# MB_Sheet1.net
KiCad netlist of a schematic drawn in Altium Designer
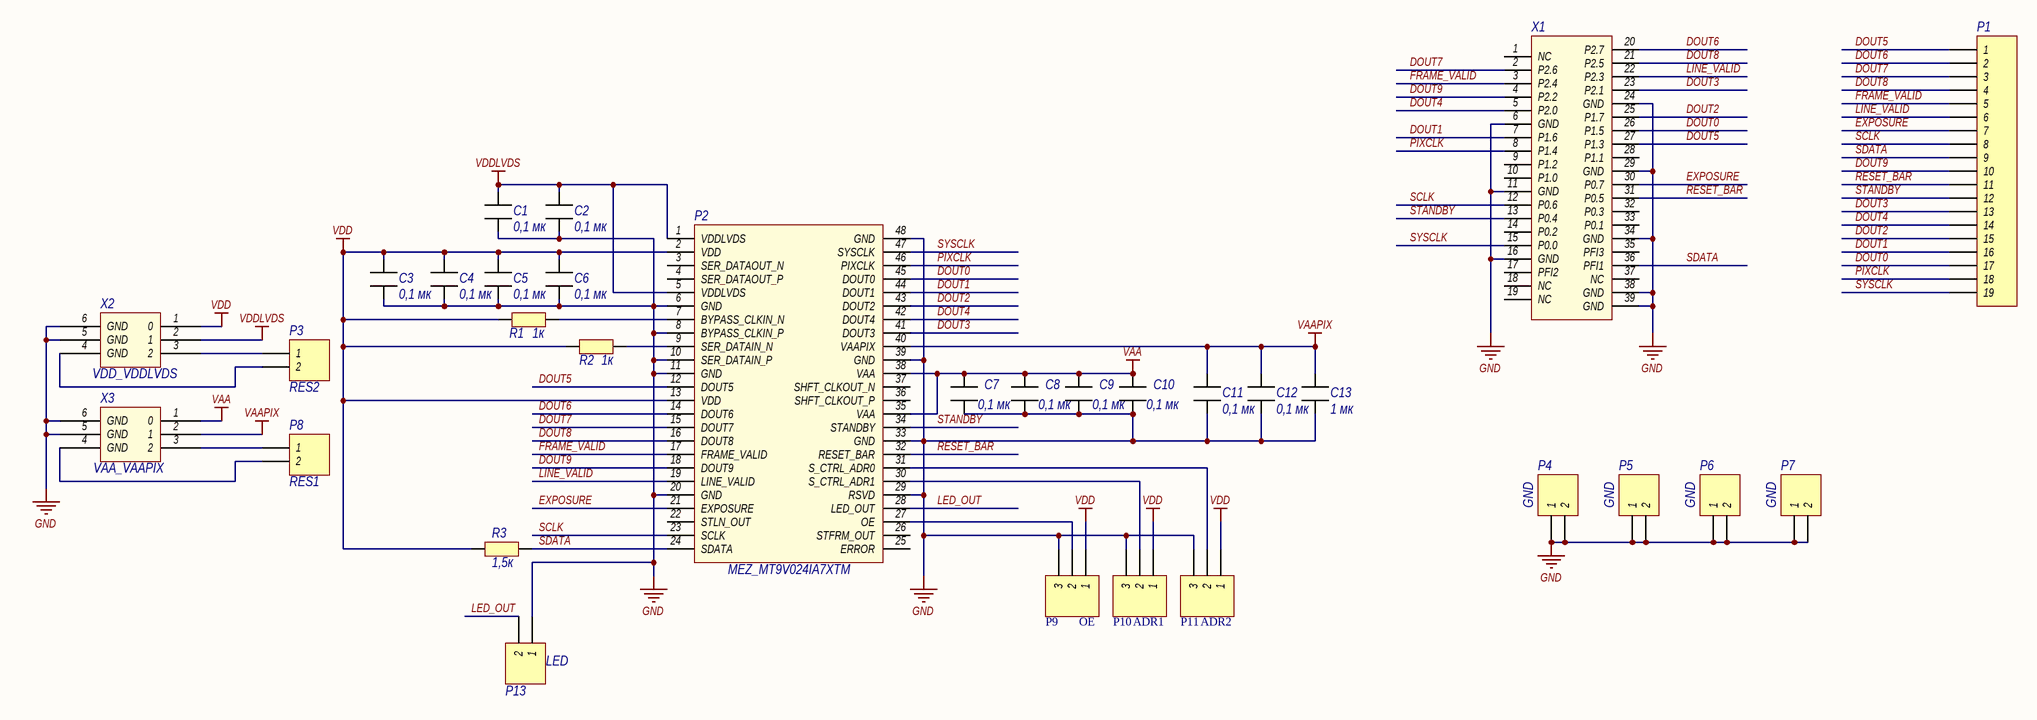
[diagram p0: MB_Sheet1.SchDoc]

(export (version "E")
  (design (tool "Eeschema 10.0.6"))
  (components
    (comp (ref "C1") (value "0,1 мк") (footprint "CAP_SMALL") (libsource (lib "Schlib") (part "CAP_SMALL")))
    (comp (ref "C2") (value "0,1 мк") (footprint "CAP_SMALL") (libsource (lib "Schlib") (part "CAP_SMALL")))
    (comp (ref "C3") (value "0,1 мк") (footprint "CAP_SMALL") (libsource (lib "Schlib") (part "CAP_SMALL")))
    (comp (ref "C4") (value "0,1 мк") (footprint "CAP_SMALL") (libsource (lib "Schlib") (part "CAP_SMALL")))
    (comp (ref "C5") (value "0,1 мк") (footprint "CAP_SMALL") (libsource (lib "Schlib") (part "CAP_SMALL")))
    (comp (ref "C6") (value "0,1 мк") (footprint "CAP_SMALL") (libsource (lib "Schlib") (part "CAP_SMALL")))
    (comp (ref "C7") (value "0,1 мк") (footprint "CAP_SMALL") (libsource (lib "Schlib") (part "CAP_SMALL")))
    (comp (ref "C8") (value "0,1 мк") (footprint "CAP_SMALL") (libsource (lib "Schlib") (part "CAP_SMALL")))
    (comp (ref "C9") (value "0,1 мк") (footprint "CAP_SMALL") (libsource (lib "Schlib") (part "CAP_SMALL")))
    (comp (ref "C10") (value "0,1 мк") (footprint "CAP_SMALL") (libsource (lib "Schlib") (part "CAP_SMALL")))
    (comp (ref "C11") (value "0,1 мк") (footprint "CAP_SMALL") (libsource (lib "Schlib") (part "CAP_SMALL")))
    (comp (ref "C12") (value "0,1 мк") (footprint "CAP_SMALL") (libsource (lib "Schlib") (part "CAP_SMALL")))
    (comp (ref "C13") (value "1 мк") (footprint "CAP_SMALL") (libsource (lib "Schlib") (part "CAP_SMALL")))
    (comp (ref "P1")
      (value "Header 19")
      (footprint "HDR1X19")
      (description "Header, 19-Pin")
      (fields (field (name "PUBLISHER") "Altium Limited"))
      (libsource (lib "Miscellaneous Connectors") (part "Header 19"))
    )
    (comp (ref "P2")
      (value "MEZ_MT9V024IA7XTM")
      (footprint "MEZ_MT9V024IA7XTM")
      (libsource (lib "Schlib") (part "MEZ_MT9V024IA7XTM"))
    )
    (comp (ref "P3")
      (value "RES2")
      (footprint "HDR1X2")
      (description "Header, 2-Pin")
      (fields (field (name "PUBLISHER") "Altium Limited"))
      (libsource (lib "") (part "Header 2_1"))
    )
    (comp (ref "P4")
      (value "GND")
      (footprint "HDR1X2")
      (description "Header, 2-Pin")
      (fields (field (name "PUBLISHER") "Altium Limited"))
      (libsource (lib "Miscellaneous Connectors") (part "Header 2"))
    )
    (comp (ref "P5")
      (value "GND")
      (footprint "HDR1X2")
      (description "Header, 2-Pin")
      (fields (field (name "PUBLISHER") "Altium Limited"))
      (libsource (lib "Miscellaneous Connectors") (part "Header 2"))
    )
    (comp (ref "P6")
      (value "GND")
      (footprint "HDR1X2")
      (description "Header, 2-Pin")
      (fields (field (name "PUBLISHER") "Altium Limited"))
      (libsource (lib "Miscellaneous Connectors") (part "Header 2"))
    )
    (comp (ref "P7")
      (value "GND")
      (footprint "HDR1X2")
      (description "Header, 2-Pin")
      (fields (field (name "PUBLISHER") "Altium Limited"))
      (libsource (lib "Miscellaneous Connectors") (part "Header 2"))
    )
    (comp (ref "P8")
      (value "RES1")
      (footprint "HDR1X2")
      (description "Header, 2-Pin")
      (fields (field (name "PUBLISHER") "Altium Limited"))
      (libsource (lib "") (part "Header 2_1"))
    )
    (comp (ref "P9")
      (value "OE")
      (footprint "HDR1X3")
      (description "Header, 3-Pin")
      (fields (field (name "PUBLISHER") "Altium Limited"))
      (libsource (lib "Miscellaneous Connectors") (part "Header 3"))
    )
    (comp (ref "P10")
      (value "ADR1")
      (footprint "HDR1X3")
      (description "Header, 3-Pin")
      (fields (field (name "PUBLISHER") "Altium Limited"))
      (libsource (lib "Miscellaneous Connectors") (part "Header 3"))
    )
    (comp (ref "P11")
      (value "ADR2")
      (footprint "HDR1X3")
      (description "Header, 3-Pin")
      (fields (field (name "PUBLISHER") "Altium Limited"))
      (libsource (lib "Miscellaneous Connectors") (part "Header 3"))
    )
    (comp (ref "P13")
      (value "LED")
      (footprint "HDR1X2")
      (description "Header, 2-Pin")
      (fields (field (name "PUBLISHER") "Altium Limited"))
      (libsource (lib "") (part "Header 2_2"))
    )
    (comp (ref "R1") (value "1к") (footprint "RES") (libsource (lib "") (part "RES_1")))
    (comp (ref "R2") (value "1к") (footprint "RES") (libsource (lib "Schlib") (part "RES")))
    (comp (ref "R3") (value "1,5к") (footprint "RES") (libsource (lib "") (part "RES_1")))
    (comp (ref "X1")
      (value "CHEAP_CON_37_FEMALE")
      (footprint "CHEAP_CONN_FEMALE")
      (libsource (lib "Schlib") (part "CHEAP_CON_37_FEMALE"))
    )
    (comp (ref "X2") (value "VDD_VDDLVDS") (footprint "POWER") (libsource (lib "Schlib") (part "POWER")))
    (comp (ref "X3") (value "VAA_VAAPIX") (footprint "POWER") (libsource (lib "Schlib") (part "POWER")))
  )
  (nets
    (net (code "1") (name "/DOUT0") (class "Default")
      (node (ref "P1") (pin "17") (pinfunction "17_17") (pintype "passive"))
      (node (ref "P2") (pin "45") (pinfunction "DOUT0_45") (pintype "passive"))
      (node (ref "X1") (pin "26") (pinfunction "P1.5_26") (pintype "passive"))
    )
    (net (code "2") (name "/DOUT1") (class "Default")
      (node (ref "P1") (pin "16") (pinfunction "16_16") (pintype "passive"))
      (node (ref "P2") (pin "44") (pinfunction "DOUT1_44") (pintype "passive"))
      (node (ref "X1") (pin "7") (pinfunction "P1.6_7") (pintype "passive"))
    )
    (net (code "3") (name "/DOUT2") (class "Default")
      (node (ref "P1") (pin "15") (pinfunction "15_15") (pintype "passive"))
      (node (ref "P2") (pin "43") (pinfunction "DOUT2_43") (pintype "passive"))
      (node (ref "X1") (pin "25") (pinfunction "P1.7_25") (pintype "passive"))
    )
    (net (code "4") (name "/DOUT3") (class "Default")
      (node (ref "P1") (pin "13") (pinfunction "13_13") (pintype "passive"))
      (node (ref "P2") (pin "41") (pinfunction "DOUT3_41") (pintype "passive"))
      (node (ref "X1") (pin "23") (pinfunction "P2.1_23") (pintype "passive"))
    )
    (net (code "5") (name "/DOUT4") (class "Default")
      (node (ref "P1") (pin "14") (pinfunction "14_14") (pintype "passive"))
      (node (ref "P2") (pin "42") (pinfunction "DOUT4_42") (pintype "passive"))
      (node (ref "X1") (pin "5") (pinfunction "P2.0_5") (pintype "passive"))
    )
    (net (code "6") (name "/DOUT5") (class "Default")
      (node (ref "P1") (pin "1") (pinfunction "1_1") (pintype "passive"))
      (node (ref "P2") (pin "12") (pinfunction "DOUT5_12") (pintype "passive"))
      (node (ref "X1") (pin "27") (pinfunction "P1.3_27") (pintype "passive"))
    )
    (net (code "7") (name "/DOUT6") (class "Default")
      (node (ref "P1") (pin "2") (pinfunction "2_2") (pintype "passive"))
      (node (ref "P2") (pin "14") (pinfunction "DOUT6_14") (pintype "passive"))
      (node (ref "X1") (pin "20") (pinfunction "P2.7_20") (pintype "passive"))
    )
    (net (code "8") (name "/DOUT7") (class "Default")
      (node (ref "P1") (pin "3") (pinfunction "3_3") (pintype "passive"))
      (node (ref "P2") (pin "15") (pinfunction "DOUT7_15") (pintype "passive"))
      (node (ref "X1") (pin "2") (pinfunction "P2.6_2") (pintype "passive"))
    )
    (net (code "9") (name "/DOUT8") (class "Default")
      (node (ref "P1") (pin "4") (pinfunction "4_4") (pintype "passive"))
      (node (ref "P2") (pin "16") (pinfunction "DOUT8_16") (pintype "passive"))
      (node (ref "X1") (pin "21") (pinfunction "P2.5_21") (pintype "passive"))
    )
    (net (code "10") (name "/DOUT9") (class "Default")
      (node (ref "P1") (pin "10") (pinfunction "10_10") (pintype "passive"))
      (node (ref "P2") (pin "18") (pinfunction "DOUT9_18") (pintype "passive"))
      (node (ref "X1") (pin "4") (pinfunction "P2.2_4") (pintype "passive"))
    )
    (net (code "11") (name "/EXPOSURE") (class "Default")
      (node (ref "P1") (pin "7") (pinfunction "7_7") (pintype "passive"))
      (node (ref "P2") (pin "21") (pinfunction "EXPOSURE_21") (pintype "passive"))
      (node (ref "X1") (pin "30") (pinfunction "P0.7_30") (pintype "passive"))
    )
    (net (code "12") (name "/FRAME_VALID") (class "Default")
      (node (ref "P1") (pin "5") (pinfunction "5_5") (pintype "passive"))
      (node (ref "P2") (pin "17") (pinfunction "FRAME_VALID_17") (pintype "passive"))
      (node (ref "X1") (pin "3") (pinfunction "P2.4_3") (pintype "passive"))
    )
    (net (code "13") (name "/LED_OUT") (class "Default")
      (node (ref "P13") (pin "2") (pinfunction "2_2") (pintype "passive"))
      (node (ref "P2") (pin "28") (pinfunction "LED_OUT_28") (pintype "passive"))
    )
    (net (code "14") (name "/LINE_VALID") (class "Default")
      (node (ref "P1") (pin "6") (pinfunction "6_6") (pintype "passive"))
      (node (ref "P2") (pin "19") (pinfunction "LINE_VALID_19") (pintype "passive"))
      (node (ref "X1") (pin "22") (pinfunction "P2.3_22") (pintype "passive"))
    )
    (net (code "15") (name "/PIXCLK") (class "Default")
      (node (ref "P1") (pin "18") (pinfunction "18_18") (pintype "passive"))
      (node (ref "P2") (pin "46") (pinfunction "PIXCLK_46") (pintype "passive"))
      (node (ref "X1") (pin "8") (pinfunction "P1.4_8") (pintype "passive"))
    )
    (net (code "16") (name "/RESET_BAR") (class "Default")
      (node (ref "P1") (pin "11") (pinfunction "11_11") (pintype "passive"))
      (node (ref "P2") (pin "32") (pinfunction "RESET_BAR_32") (pintype "passive"))
      (node (ref "X1") (pin "31") (pinfunction "P0.5_31") (pintype "passive"))
    )
    (net (code "17") (name "/SCLK") (class "Default")
      (node (ref "P1") (pin "8") (pinfunction "8_8") (pintype "passive"))
      (node (ref "P2") (pin "23") (pinfunction "SCLK_23") (pintype "passive"))
      (node (ref "X1") (pin "12") (pinfunction "P0.6_12") (pintype "passive"))
    )
    (net (code "18") (name "/SDATA") (class "Default")
      (node (ref "P1") (pin "9") (pinfunction "9_9") (pintype "passive"))
      (node (ref "P2") (pin "24") (pinfunction "SDATA_24") (pintype "passive"))
      (node (ref "R3") (pin "2") (pinfunction "2_2") (pintype "passive"))
      (node (ref "X1") (pin "36") (pinfunction "PFI1_36") (pintype "passive"))
    )
    (net (code "19") (name "/STANDBY") (class "Default")
      (node (ref "P1") (pin "12") (pinfunction "12_12") (pintype "passive"))
      (node (ref "P2") (pin "34") (pinfunction "STANDBY_34") (pintype "passive"))
      (node (ref "X1") (pin "13") (pinfunction "P0.4_13") (pintype "passive"))
    )
    (net (code "20") (name "/SYSCLK") (class "Default")
      (node (ref "P1") (pin "19") (pinfunction "19_19") (pintype "passive"))
      (node (ref "P2") (pin "47") (pinfunction "SYSCLK_47") (pintype "passive"))
      (node (ref "X1") (pin "15") (pinfunction "P0.0_15") (pintype "passive"))
    )
    (net (code "21") (name "GND") (class "Default")
      (node (ref "C1") (pin "1") (pinfunction "1_1") (pintype "passive"))
      (node (ref "C10") (pin "1") (pinfunction "1_1") (pintype "passive"))
      (node (ref "C11") (pin "1") (pinfunction "1_1") (pintype "passive"))
      (node (ref "C12") (pin "1") (pinfunction "1_1") (pintype "passive"))
      (node (ref "C13") (pin "1") (pinfunction "1_1") (pintype "passive"))
      (node (ref "C2") (pin "1") (pinfunction "1_1") (pintype "passive"))
      (node (ref "C3") (pin "1") (pinfunction "1_1") (pintype "passive"))
      (node (ref "C4") (pin "1") (pinfunction "1_1") (pintype "passive"))
      (node (ref "C5") (pin "1") (pinfunction "1_1") (pintype "passive"))
      (node (ref "C6") (pin "1") (pinfunction "1_1") (pintype "passive"))
      (node (ref "C7") (pin "1") (pinfunction "1_1") (pintype "passive"))
      (node (ref "C8") (pin "1") (pinfunction "1_1") (pintype "passive"))
      (node (ref "C9") (pin "1") (pinfunction "1_1") (pintype "passive"))
      (node (ref "P10") (pin "3") (pinfunction "3_3") (pintype "passive"))
      (node (ref "P11") (pin "3") (pinfunction "3_3") (pintype "passive"))
      (node (ref "P13") (pin "1") (pinfunction "1_1") (pintype "passive"))
      (node (ref "P2") (pin "10") (pinfunction "SER_DATAIN_P_10") (pintype "passive"))
      (node (ref "P2") (pin "11") (pinfunction "GND_11") (pintype "passive"))
      (node (ref "P2") (pin "20") (pinfunction "GND_20") (pintype "passive"))
      (node (ref "P2") (pin "29") (pinfunction "RSVD_29") (pintype "passive"))
      (node (ref "P2") (pin "33") (pinfunction "GND_33") (pintype "passive"))
      (node (ref "P2") (pin "39") (pinfunction "GND_39") (pintype "passive"))
      (node (ref "P2") (pin "48") (pinfunction "GND_48") (pintype "passive"))
      (node (ref "P2") (pin "6") (pinfunction "GND_6") (pintype "passive"))
      (node (ref "P2") (pin "8") (pinfunction "BYPASS_CLKIN_P_8") (pintype "passive"))
      (node (ref "P4") (pin "1") (pinfunction "1_1") (pintype "passive"))
      (node (ref "P4") (pin "2") (pinfunction "2_2") (pintype "passive"))
      (node (ref "P5") (pin "1") (pinfunction "1_1") (pintype "passive"))
      (node (ref "P5") (pin "2") (pinfunction "2_2") (pintype "passive"))
      (node (ref "P6") (pin "1") (pinfunction "1_1") (pintype "passive"))
      (node (ref "P6") (pin "2") (pinfunction "2_2") (pintype "passive"))
      (node (ref "P7") (pin "1") (pinfunction "1_1") (pintype "passive"))
      (node (ref "P7") (pin "2") (pinfunction "2_2") (pintype "passive"))
      (node (ref "P9") (pin "3") (pinfunction "3_3") (pintype "passive"))
      (node (ref "X1") (pin "11") (pinfunction "GND_11") (pintype "passive"))
      (node (ref "X1") (pin "16") (pinfunction "GND_16") (pintype "passive"))
      (node (ref "X1") (pin "24") (pinfunction "GND_24") (pintype "passive"))
      (node (ref "X1") (pin "29") (pinfunction "GND_29") (pintype "passive"))
      (node (ref "X1") (pin "34") (pinfunction "GND_34") (pintype "passive"))
      (node (ref "X1") (pin "38") (pinfunction "GND_38") (pintype "passive"))
      (node (ref "X1") (pin "39") (pinfunction "GND_39") (pintype "passive"))
      (node (ref "X1") (pin "6") (pinfunction "GND_6") (pintype "passive"))
      (node (ref "X2") (pin "5") (pinfunction "GND_5") (pintype "passive"))
      (node (ref "X2") (pin "6") (pinfunction "GND_6") (pintype "passive"))
      (node (ref "X3") (pin "5") (pinfunction "GND_5") (pintype "passive"))
      (node (ref "X3") (pin "6") (pinfunction "GND_6") (pintype "passive"))
    )
    (net (code "22") (name "Net-(P2-BYPASS_CLKIN_N)") (class "Default")
      (node (ref "P2") (pin "7") (pinfunction "BYPASS_CLKIN_N_7") (pintype "passive"))
      (node (ref "R1") (pin "2") (pinfunction "2_2") (pintype "passive"))
    )
    (net (code "23") (name "Net-(P2-OE)") (class "Default")
      (node (ref "P2") (pin "27") (pinfunction "OE_27") (pintype "passive"))
      (node (ref "P9") (pin "2") (pinfunction "2_2") (pintype "passive"))
    )
    (net (code "24") (name "Net-(P2-SER_DATAIN_N)") (class "Default")
      (node (ref "P2") (pin "9") (pinfunction "SER_DATAIN_N_9") (pintype "passive"))
      (node (ref "R2") (pin "1") (pinfunction "1_1") (pintype "passive"))
    )
    (net (code "25") (name "Net-(P2-S_CTRL_ADR0)") (class "Default")
      (node (ref "P11") (pin "2") (pinfunction "2_2") (pintype "passive"))
      (node (ref "P2") (pin "31") (pinfunction "S_CTRL_ADR0_31") (pintype "passive"))
    )
    (net (code "26") (name "Net-(P2-S_CTRL_ADR1)") (class "Default")
      (node (ref "P10") (pin "2") (pinfunction "2_2") (pintype "passive"))
      (node (ref "P2") (pin "30") (pinfunction "S_CTRL_ADR1_30") (pintype "passive"))
    )
    (net (code "27") (name "Net-(P3-Pad2)") (class "Default")
      (node (ref "P3") (pin "2") (pinfunction "2_2") (pintype "passive"))
      (node (ref "X2") (pin "4") (pinfunction "GND_4") (pintype "passive"))
    )
    (net (code "28") (name "Net-(P8-Pad2)") (class "Default")
      (node (ref "P8") (pin "2") (pinfunction "2_2") (pintype "passive"))
      (node (ref "X3") (pin "4") (pinfunction "GND_4") (pintype "passive"))
    )
    (net (code "29") (name "Net-(X2-2)") (class "Default")
      (node (ref "P3") (pin "1") (pinfunction "1_1") (pintype "passive"))
      (node (ref "X2") (pin "3") (pinfunction "2_3") (pintype "passive"))
    )
    (net (code "30") (name "Net-(X3-2)") (class "Default")
      (node (ref "P8") (pin "1") (pinfunction "1_1") (pintype "passive"))
      (node (ref "X3") (pin "3") (pinfunction "2_3") (pintype "passive"))
    )
    (net (code "31") (name "VAA") (class "Default")
      (node (ref "C10") (pin "2") (pinfunction "2_2") (pintype "passive"))
      (node (ref "C7") (pin "2") (pinfunction "2_2") (pintype "passive"))
      (node (ref "C8") (pin "2") (pinfunction "2_2") (pintype "passive"))
      (node (ref "C9") (pin "2") (pinfunction "2_2") (pintype "passive"))
      (node (ref "P2") (pin "35") (pinfunction "VAA_35") (pintype "passive"))
      (node (ref "P2") (pin "38") (pinfunction "VAA_38") (pintype "passive"))
      (node (ref "X3") (pin "1") (pinfunction "0_1") (pintype "passive"))
    )
    (net (code "32") (name "VAAPIX") (class "Default")
      (node (ref "C11") (pin "2") (pinfunction "2_2") (pintype "passive"))
      (node (ref "C12") (pin "2") (pinfunction "2_2") (pintype "passive"))
      (node (ref "C13") (pin "2") (pinfunction "2_2") (pintype "passive"))
      (node (ref "P2") (pin "40") (pinfunction "VAAPIX_40") (pintype "passive"))
      (node (ref "X3") (pin "2") (pinfunction "1_2") (pintype "passive"))
    )
    (net (code "33") (name "VDD") (class "Default")
      (node (ref "C3") (pin "2") (pinfunction "2_2") (pintype "passive"))
      (node (ref "C4") (pin "2") (pinfunction "2_2") (pintype "passive"))
      (node (ref "C5") (pin "2") (pinfunction "2_2") (pintype "passive"))
      (node (ref "C6") (pin "2") (pinfunction "2_2") (pintype "passive"))
      (node (ref "P10") (pin "1") (pinfunction "1_1") (pintype "passive"))
      (node (ref "P11") (pin "1") (pinfunction "1_1") (pintype "passive"))
      (node (ref "P2") (pin "13") (pinfunction "VDD_13") (pintype "passive"))
      (node (ref "P2") (pin "2") (pinfunction "VDD_2") (pintype "passive"))
      (node (ref "P9") (pin "1") (pinfunction "1_1") (pintype "passive"))
      (node (ref "R1") (pin "1") (pinfunction "1_1") (pintype "passive"))
      (node (ref "R2") (pin "2") (pinfunction "2_2") (pintype "passive"))
      (node (ref "R3") (pin "1") (pinfunction "1_1") (pintype "passive"))
      (node (ref "X2") (pin "1") (pinfunction "0_1") (pintype "passive"))
    )
    (net (code "34") (name "VDDLVDS") (class "Default")
      (node (ref "C1") (pin "2") (pinfunction "2_2") (pintype "passive"))
      (node (ref "C2") (pin "2") (pinfunction "2_2") (pintype "passive"))
      (node (ref "P2") (pin "1") (pinfunction "VDDLVDS_1") (pintype "passive"))
      (node (ref "P2") (pin "5") (pinfunction "VDDLVDS_5") (pintype "passive"))
      (node (ref "X2") (pin "2") (pinfunction "1_2") (pintype "passive"))
    )
    (net (code "35") (name "unconnected-(P2-ERROR-Pad25)") (class "Default")
      (node (ref "P2") (pin "25") (pinfunction "ERROR_25") (pintype "passive"))
    )
    (net (code "36") (name "unconnected-(P2-SER_DATAOUT_N-Pad3)") (class "Default")
      (node (ref "P2") (pin "3") (pinfunction "SER_DATAOUT_N_3") (pintype "passive"))
    )
    (net (code "37") (name "unconnected-(P2-SER_DATAOUT_P-Pad4)") (class "Default")
      (node (ref "P2") (pin "4") (pinfunction "SER_DATAOUT_P_4") (pintype "passive"))
    )
    (net (code "38") (name "unconnected-(P2-SHFT_CLKOUT_N-Pad37)") (class "Default")
      (node (ref "P2") (pin "37") (pinfunction "SHFT_CLKOUT_N_37") (pintype "passive"))
    )
    (net (code "39") (name "unconnected-(P2-SHFT_CLKOUT_P-Pad36)") (class "Default")
      (node (ref "P2") (pin "36") (pinfunction "SHFT_CLKOUT_P_36") (pintype "passive"))
    )
    (net (code "40") (name "unconnected-(P2-STFRM_OUT-Pad26)") (class "Default")
      (node (ref "P2") (pin "26") (pinfunction "STFRM_OUT_26") (pintype "passive"))
    )
    (net (code "41") (name "unconnected-(P2-STLN_OUT-Pad22)") (class "Default")
      (node (ref "P2") (pin "22") (pinfunction "STLN_OUT_22") (pintype "passive"))
    )
    (net (code "42") (name "unconnected-(X1-NC-Pad1)") (class "Default")
      (node (ref "X1") (pin "1") (pinfunction "NC_1") (pintype "passive"))
    )
    (net (code "43") (name "unconnected-(X1-NC-Pad18)") (class "Default")
      (node (ref "X1") (pin "18") (pinfunction "NC_18") (pintype "passive"))
    )
    (net (code "44") (name "unconnected-(X1-NC-Pad19)") (class "Default")
      (node (ref "X1") (pin "19") (pinfunction "NC_19") (pintype "passive"))
    )
    (net (code "45") (name "unconnected-(X1-NC-Pad37)") (class "Default")
      (node (ref "X1") (pin "37") (pinfunction "NC_37") (pintype "passive"))
    )
    (net (code "46") (name "unconnected-(X1-P0.1-Pad33)") (class "Default")
      (node (ref "X1") (pin "33") (pinfunction "P0.1_33") (pintype "passive"))
    )
    (net (code "47") (name "unconnected-(X1-P0.2-Pad14)") (class "Default")
      (node (ref "X1") (pin "14") (pinfunction "P0.2_14") (pintype "passive"))
    )
    (net (code "48") (name "unconnected-(X1-P0.3-Pad32)") (class "Default")
      (node (ref "X1") (pin "32") (pinfunction "P0.3_32") (pintype "passive"))
    )
    (net (code "49") (name "unconnected-(X1-P1.0-Pad10)") (class "Default")
      (node (ref "X1") (pin "10") (pinfunction "P1.0_10") (pintype "passive"))
    )
    (net (code "50") (name "unconnected-(X1-P1.1-Pad28)") (class "Default")
      (node (ref "X1") (pin "28") (pinfunction "P1.1_28") (pintype "passive"))
    )
    (net (code "51") (name "unconnected-(X1-P1.2-Pad9)") (class "Default")
      (node (ref "X1") (pin "9") (pinfunction "P1.2_9") (pintype "passive"))
    )
    (net (code "52") (name "unconnected-(X1-PFI2-Pad17)") (class "Default")
      (node (ref "X1") (pin "17") (pinfunction "PFI2_17") (pintype "passive"))
    )
    (net (code "53") (name "unconnected-(X1-PFI3-Pad35)") (class "Default")
      (node (ref "X1") (pin "35") (pinfunction "PFI3_35") (pintype "passive"))
    )
  )
)
